# Display.net
KiCad netlist of a schematic drawn in Altium Designer
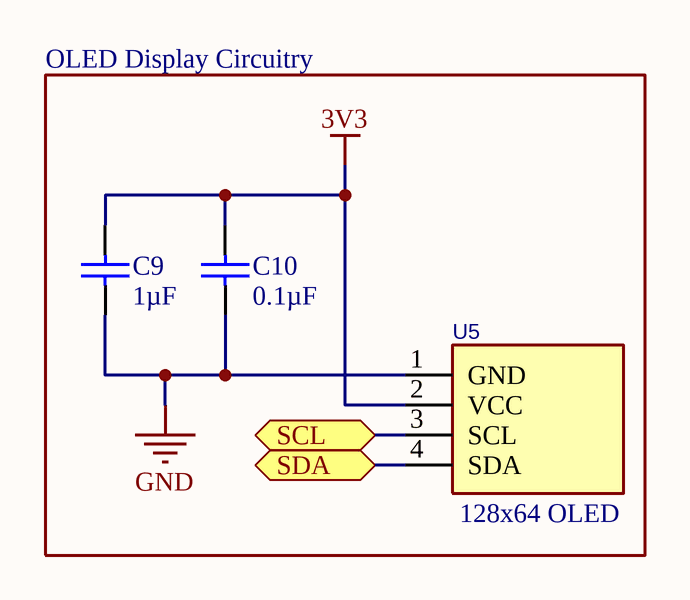
[diagram p0: Display.SchDoc]

(export (version "E")
  (design (tool "Eeschema 10.0.6"))
  (components
    (comp (ref "C9")
      (value "1µF")
      (footprint "CAPC3216X110X50LL20T25")
      (description "Chip Capacitor, 1 uF, +/- 10%, 50 V, -55 to 125 degC, 1206 (3216 Metric), RoHS, Tape and Reel")
      (fields (field (name "MANUFACTURER") "Kemet") (field (name "TOLERANCE") "10%"))
      (libsource (lib "") (part "CAP-NP-2_1"))
    )
    (comp (ref "C10")
      (value "0.1µF")
      (footprint "CAPC3216X100X50LL20T25")
      (description "Chip Capacitor, 100 nF, +/- 10%, 25 V, -55 to 125 degC, 1206 (3216 Metric), RoHS, Tape and Reel")
      (fields (field (name "MANUFACTURER") "Kemet"))
      (libsource (lib "Altium Content Vault") (part "CAP-NP-2"))
    )
    (comp (ref "U5")
      (value "128x64 OLED")
      (footprint "Amazon OLED Display Module")
      (description "Hosyond 5 Pcs 0.96 Inch OLED I2C Display Module 128x64 Pixel OLED Display")
      (libsource (lib "RIT-EVT-Vault") (part "Amazon OLED Display Module"))
    )
  )
  (nets
    (net (code "1") (name "/SCL") (class "Default")
      (node (ref "U5") (pin "3") (pinfunction "SCL_3") (pintype "passive"))
    )
    (net (code "2") (name "/SDA") (class "Default")
      (node (ref "U5") (pin "4") (pinfunction "SDA_4") (pintype "passive"))
    )
    (net (code "3") (name "3V3") (class "Default")
      (node (ref "C10") (pin "2") (pinfunction "2_2") (pintype "passive"))
      (node (ref "C9") (pin "2") (pinfunction "2_2") (pintype "passive"))
      (node (ref "U5") (pin "2") (pinfunction "VCC_2") (pintype "passive"))
    )
    (net (code "4") (name "GND") (class "Default")
      (node (ref "C10") (pin "1") (pinfunction "1_1") (pintype "passive"))
      (node (ref "C9") (pin "1") (pinfunction "1_1") (pintype "passive"))
      (node (ref "U5") (pin "1") (pinfunction "GND_1") (pintype "passive"))
    )
  )
)
